# Jumper_Board_V3_0.net
KiCad netlist of a schematic drawn in EAGLE
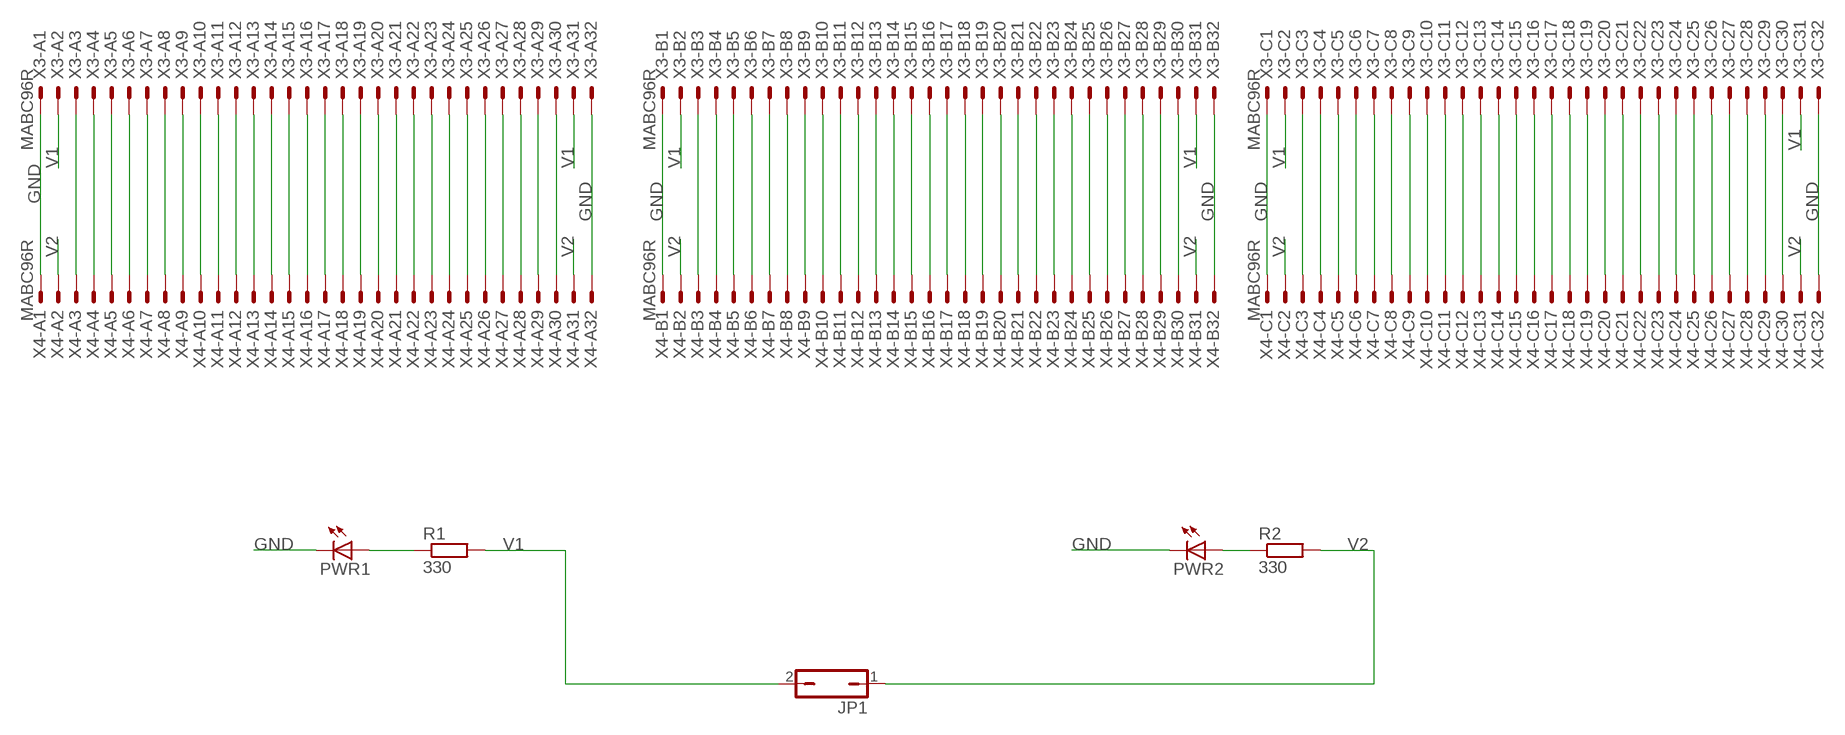
[diagram p0: schematic, sheet 1]

(export (version "E")
  (design (tool "Eeschema 10.0.6"))
  (components
    (comp (ref "JP1")
      (value "JP1Q")
      (footprint "eagle-import:JP1")
      (libsource (lib "eagle-import") (part "JP1Q"))
    )
    (comp (ref "PWR1")
      (value "LED5MM")
      (footprint "eagle-import:LED5MM")
      (libsource (lib "eagle-import") (part "LED5MM"))
    )
    (comp (ref "PWR2")
      (value "LED5MM")
      (footprint "eagle-import:LED5MM")
      (libsource (lib "eagle-import") (part "LED5MM"))
    )
    (comp (ref "R1")
      (value "330")
      (footprint "eagle-import:0207_10")
      (libsource (lib "eagle-import") (part "R0207/10"))
    )
    (comp (ref "R2")
      (value "330")
      (footprint "eagle-import:0207_10")
      (libsource (lib "eagle-import") (part "R0207/10"))
    )
    (comp (ref "X3")
      (value "MABC96R")
      (footprint "eagle-import:MABC96R")
      (libsource (lib "eagle-import") (part "MABC96R"))
    )
    (comp (ref "X4")
      (value "MABC96R")
      (footprint "eagle-import:MABC96R")
      (libsource (lib "eagle-import") (part "MABC96R"))
    )
  )
  (nets
    (net (code "1") (name "/GND") (class "Default")
      (node (ref "PWR1") (pin "K") (pinfunction "C_K") (pintype "passive"))
      (node (ref "PWR2") (pin "K") (pinfunction "C_K") (pintype "passive"))
      (node (ref "X3") (pin "A1") (pinfunction "S_A1") (pintype "passive"))
      (node (ref "X3") (pin "A32") (pinfunction "S_A32") (pintype "passive"))
      (node (ref "X3") (pin "B1") (pinfunction "S_B1") (pintype "passive"))
      (node (ref "X3") (pin "B32") (pinfunction "S_B32") (pintype "passive"))
      (node (ref "X3") (pin "C1") (pinfunction "S_C1") (pintype "passive"))
      (node (ref "X3") (pin "C32") (pinfunction "S_C32") (pintype "passive"))
      (node (ref "X4") (pin "A1") (pinfunction "S_A1") (pintype "passive"))
      (node (ref "X4") (pin "A32") (pinfunction "S_A32") (pintype "passive"))
      (node (ref "X4") (pin "B1") (pinfunction "S_B1") (pintype "passive"))
      (node (ref "X4") (pin "B32") (pinfunction "S_B32") (pintype "passive"))
      (node (ref "X4") (pin "C1") (pinfunction "S_C1") (pintype "passive"))
      (node (ref "X4") (pin "C32") (pinfunction "S_C32") (pintype "passive"))
    )
    (net (code "2") (name "/V1") (class "Default")
      (node (ref "JP1") (pin "2") (pinfunction "2_2") (pintype "passive"))
      (node (ref "R1") (pin "2") (pinfunction "2_2") (pintype "passive"))
      (node (ref "X3") (pin "A2") (pinfunction "S_A2") (pintype "passive"))
      (node (ref "X3") (pin "A31") (pinfunction "S_A31") (pintype "passive"))
      (node (ref "X3") (pin "B2") (pinfunction "S_B2") (pintype "passive"))
      (node (ref "X3") (pin "B31") (pinfunction "S_B31") (pintype "passive"))
      (node (ref "X3") (pin "C2") (pinfunction "S_C2") (pintype "passive"))
      (node (ref "X3") (pin "C31") (pinfunction "S_C31") (pintype "passive"))
    )
    (net (code "3") (name "/V2") (class "Default")
      (node (ref "JP1") (pin "1") (pinfunction "1_1") (pintype "passive"))
      (node (ref "R2") (pin "2") (pinfunction "2_2") (pintype "passive"))
      (node (ref "X4") (pin "A2") (pinfunction "S_A2") (pintype "passive"))
      (node (ref "X4") (pin "A31") (pinfunction "S_A31") (pintype "passive"))
      (node (ref "X4") (pin "B2") (pinfunction "S_B2") (pintype "passive"))
      (node (ref "X4") (pin "B31") (pinfunction "S_B31") (pintype "passive"))
      (node (ref "X4") (pin "C2") (pinfunction "S_C2") (pintype "passive"))
      (node (ref "X4") (pin "C31") (pinfunction "S_C31") (pintype "passive"))
    )
    (net (code "4") (name "Net-(PWR1-PadA)") (class "Default")
      (node (ref "PWR1") (pin "A") (pinfunction "A_A") (pintype "passive"))
      (node (ref "R1") (pin "1") (pinfunction "1_1") (pintype "passive"))
    )
    (net (code "5") (name "Net-(PWR2-PadA)") (class "Default")
      (node (ref "PWR2") (pin "A") (pinfunction "A_A") (pintype "passive"))
      (node (ref "R2") (pin "1") (pinfunction "1_1") (pintype "passive"))
    )
    (net (code "6") (name "Net-(X3AA-S)") (class "Default")
      (node (ref "X3") (pin "A4") (pinfunction "S_A4") (pintype "passive"))
      (node (ref "X4") (pin "A4") (pinfunction "S_A4") (pintype "passive"))
    )
    (net (code "7") (name "Net-(X3AB-S)") (class "Default")
      (node (ref "X3") (pin "A5") (pinfunction "S_A5") (pintype "passive"))
      (node (ref "X4") (pin "A5") (pinfunction "S_A5") (pintype "passive"))
    )
    (net (code "8") (name "Net-(X3AC-S)") (class "Default")
      (node (ref "X3") (pin "A6") (pinfunction "S_A6") (pintype "passive"))
      (node (ref "X4") (pin "A6") (pinfunction "S_A6") (pintype "passive"))
    )
    (net (code "9") (name "Net-(X3AD-S)") (class "Default")
      (node (ref "X3") (pin "A7") (pinfunction "S_A7") (pintype "passive"))
      (node (ref "X4") (pin "A7") (pinfunction "S_A7") (pintype "passive"))
    )
    (net (code "10") (name "Net-(X3AE-S)") (class "Default")
      (node (ref "X3") (pin "A8") (pinfunction "S_A8") (pintype "passive"))
      (node (ref "X4") (pin "A8") (pinfunction "S_A8") (pintype "passive"))
    )
    (net (code "11") (name "Net-(X3AF-S)") (class "Default")
      (node (ref "X3") (pin "A9") (pinfunction "S_A9") (pintype "passive"))
      (node (ref "X4") (pin "A9") (pinfunction "S_A9") (pintype "passive"))
    )
    (net (code "12") (name "Net-(X3AH-S)") (class "Default")
      (node (ref "X3") (pin "B10") (pinfunction "S_B10") (pintype "passive"))
      (node (ref "X4") (pin "B10") (pinfunction "S_B10") (pintype "passive"))
    )
    (net (code "13") (name "Net-(X3AI-S)") (class "Default")
      (node (ref "X3") (pin "B11") (pinfunction "S_B11") (pintype "passive"))
      (node (ref "X4") (pin "B11") (pinfunction "S_B11") (pintype "passive"))
    )
    (net (code "14") (name "Net-(X3AJ-S)") (class "Default")
      (node (ref "X3") (pin "B12") (pinfunction "S_B12") (pintype "passive"))
      (node (ref "X4") (pin "B12") (pinfunction "S_B12") (pintype "passive"))
    )
    (net (code "15") (name "Net-(X3AK-S)") (class "Default")
      (node (ref "X3") (pin "B13") (pinfunction "S_B13") (pintype "passive"))
      (node (ref "X4") (pin "B13") (pinfunction "S_B13") (pintype "passive"))
    )
    (net (code "16") (name "Net-(X3AL-S)") (class "Default")
      (node (ref "X3") (pin "B14") (pinfunction "S_B14") (pintype "passive"))
      (node (ref "X4") (pin "B14") (pinfunction "S_B14") (pintype "passive"))
    )
    (net (code "17") (name "Net-(X3AM-S)") (class "Default")
      (node (ref "X3") (pin "B15") (pinfunction "S_B15") (pintype "passive"))
      (node (ref "X4") (pin "B15") (pinfunction "S_B15") (pintype "passive"))
    )
    (net (code "18") (name "Net-(X3AN-S)") (class "Default")
      (node (ref "X3") (pin "B16") (pinfunction "S_B16") (pintype "passive"))
      (node (ref "X4") (pin "B16") (pinfunction "S_B16") (pintype "passive"))
    )
    (net (code "19") (name "Net-(X3AO-S)") (class "Default")
      (node (ref "X3") (pin "B17") (pinfunction "S_B17") (pintype "passive"))
      (node (ref "X4") (pin "B17") (pinfunction "S_B17") (pintype "passive"))
    )
    (net (code "20") (name "Net-(X3AP-S)") (class "Default")
      (node (ref "X3") (pin "B18") (pinfunction "S_B18") (pintype "passive"))
      (node (ref "X4") (pin "B18") (pinfunction "S_B18") (pintype "passive"))
    )
    (net (code "21") (name "Net-(X3AQ-S)") (class "Default")
      (node (ref "X3") (pin "B19") (pinfunction "S_B19") (pintype "passive"))
      (node (ref "X4") (pin "B19") (pinfunction "S_B19") (pintype "passive"))
    )
    (net (code "22") (name "Net-(X3AS-S)") (class "Default")
      (node (ref "X3") (pin "B20") (pinfunction "S_B20") (pintype "passive"))
      (node (ref "X4") (pin "B20") (pinfunction "S_B20") (pintype "passive"))
    )
    (net (code "23") (name "Net-(X3AT-S)") (class "Default")
      (node (ref "X3") (pin "B21") (pinfunction "S_B21") (pintype "passive"))
      (node (ref "X4") (pin "B21") (pinfunction "S_B21") (pintype "passive"))
    )
    (net (code "24") (name "Net-(X3AU-S)") (class "Default")
      (node (ref "X3") (pin "B22") (pinfunction "S_B22") (pintype "passive"))
      (node (ref "X4") (pin "B22") (pinfunction "S_B22") (pintype "passive"))
    )
    (net (code "25") (name "Net-(X3AV-S)") (class "Default")
      (node (ref "X3") (pin "B23") (pinfunction "S_B23") (pintype "passive"))
      (node (ref "X4") (pin "B23") (pinfunction "S_B23") (pintype "passive"))
    )
    (net (code "26") (name "Net-(X3AW-S)") (class "Default")
      (node (ref "X3") (pin "B24") (pinfunction "S_B24") (pintype "passive"))
      (node (ref "X4") (pin "B24") (pinfunction "S_B24") (pintype "passive"))
    )
    (net (code "27") (name "Net-(X3AX-S)") (class "Default")
      (node (ref "X3") (pin "B25") (pinfunction "S_B25") (pintype "passive"))
      (node (ref "X4") (pin "B25") (pinfunction "S_B25") (pintype "passive"))
    )
    (net (code "28") (name "Net-(X3AY-S)") (class "Default")
      (node (ref "X3") (pin "B26") (pinfunction "S_B26") (pintype "passive"))
      (node (ref "X4") (pin "B26") (pinfunction "S_B26") (pintype "passive"))
    )
    (net (code "29") (name "Net-(X3AZ-S)") (class "Default")
      (node (ref "X3") (pin "B27") (pinfunction "S_B27") (pintype "passive"))
      (node (ref "X4") (pin "B27") (pinfunction "S_B27") (pintype "passive"))
    )
    (net (code "30") (name "Net-(X3B-S)") (class "Default")
      (node (ref "X3") (pin "A10") (pinfunction "S_A10") (pintype "passive"))
      (node (ref "X4") (pin "A10") (pinfunction "S_A10") (pintype "passive"))
    )
    (net (code "31") (name "Net-(X3BA-S)") (class "Default")
      (node (ref "X3") (pin "B28") (pinfunction "S_B28") (pintype "passive"))
      (node (ref "X4") (pin "B28") (pinfunction "S_B28") (pintype "passive"))
    )
    (net (code "32") (name "Net-(X3BB-S)") (class "Default")
      (node (ref "X3") (pin "B29") (pinfunction "S_B29") (pintype "passive"))
      (node (ref "X4") (pin "B29") (pinfunction "S_B29") (pintype "passive"))
    )
    (net (code "33") (name "Net-(X3BC-S)") (class "Default")
      (node (ref "X3") (pin "B3") (pinfunction "S_B3") (pintype "passive"))
      (node (ref "X4") (pin "B3") (pinfunction "S_B3") (pintype "passive"))
    )
    (net (code "34") (name "Net-(X3BD-S)") (class "Default")
      (node (ref "X3") (pin "B30") (pinfunction "S_B30") (pintype "passive"))
      (node (ref "X4") (pin "B30") (pinfunction "S_B30") (pintype "passive"))
    )
    (net (code "35") (name "Net-(X3BG-S)") (class "Default")
      (node (ref "X3") (pin "B4") (pinfunction "S_B4") (pintype "passive"))
      (node (ref "X4") (pin "B4") (pinfunction "S_B4") (pintype "passive"))
    )
    (net (code "36") (name "Net-(X3BH-S)") (class "Default")
      (node (ref "X3") (pin "B5") (pinfunction "S_B5") (pintype "passive"))
      (node (ref "X4") (pin "B5") (pinfunction "S_B5") (pintype "passive"))
    )
    (net (code "37") (name "Net-(X3BI-S)") (class "Default")
      (node (ref "X3") (pin "B6") (pinfunction "S_B6") (pintype "passive"))
      (node (ref "X4") (pin "B6") (pinfunction "S_B6") (pintype "passive"))
    )
    (net (code "38") (name "Net-(X3BJ-S)") (class "Default")
      (node (ref "X3") (pin "B7") (pinfunction "S_B7") (pintype "passive"))
      (node (ref "X4") (pin "B7") (pinfunction "S_B7") (pintype "passive"))
    )
    (net (code "39") (name "Net-(X3BK-S)") (class "Default")
      (node (ref "X3") (pin "B8") (pinfunction "S_B8") (pintype "passive"))
      (node (ref "X4") (pin "B8") (pinfunction "S_B8") (pintype "passive"))
    )
    (net (code "40") (name "Net-(X3BL-S)") (class "Default")
      (node (ref "X3") (pin "B9") (pinfunction "S_B9") (pintype "passive"))
      (node (ref "X4") (pin "B9") (pinfunction "S_B9") (pintype "passive"))
    )
    (net (code "41") (name "Net-(X3BN-S)") (class "Default")
      (node (ref "X3") (pin "C10") (pinfunction "S_C10") (pintype "passive"))
      (node (ref "X4") (pin "C10") (pinfunction "S_C10") (pintype "passive"))
    )
    (net (code "42") (name "Net-(X3BO-S)") (class "Default")
      (node (ref "X3") (pin "C11") (pinfunction "S_C11") (pintype "passive"))
      (node (ref "X4") (pin "C11") (pinfunction "S_C11") (pintype "passive"))
    )
    (net (code "43") (name "Net-(X3BP-S)") (class "Default")
      (node (ref "X3") (pin "C12") (pinfunction "S_C12") (pintype "passive"))
      (node (ref "X4") (pin "C12") (pinfunction "S_C12") (pintype "passive"))
    )
    (net (code "44") (name "Net-(X3BQ-S)") (class "Default")
      (node (ref "X3") (pin "C13") (pinfunction "S_C13") (pintype "passive"))
      (node (ref "X4") (pin "C13") (pinfunction "S_C13") (pintype "passive"))
    )
    (net (code "45") (name "Net-(X3BR-S)") (class "Default")
      (node (ref "X3") (pin "C14") (pinfunction "S_C14") (pintype "passive"))
      (node (ref "X4") (pin "C14") (pinfunction "S_C14") (pintype "passive"))
    )
    (net (code "46") (name "Net-(X3BS-S)") (class "Default")
      (node (ref "X3") (pin "C15") (pinfunction "S_C15") (pintype "passive"))
      (node (ref "X4") (pin "C15") (pinfunction "S_C15") (pintype "passive"))
    )
    (net (code "47") (name "Net-(X3BT-S)") (class "Default")
      (node (ref "X3") (pin "C16") (pinfunction "S_C16") (pintype "passive"))
      (node (ref "X4") (pin "C16") (pinfunction "S_C16") (pintype "passive"))
    )
    (net (code "48") (name "Net-(X3BU-S)") (class "Default")
      (node (ref "X3") (pin "C17") (pinfunction "S_C17") (pintype "passive"))
      (node (ref "X4") (pin "C17") (pinfunction "S_C17") (pintype "passive"))
    )
    (net (code "49") (name "Net-(X3BV-S)") (class "Default")
      (node (ref "X3") (pin "C18") (pinfunction "S_C18") (pintype "passive"))
      (node (ref "X4") (pin "C18") (pinfunction "S_C18") (pintype "passive"))
    )
    (net (code "50") (name "Net-(X3BW-S)") (class "Default")
      (node (ref "X3") (pin "C19") (pinfunction "S_C19") (pintype "passive"))
      (node (ref "X4") (pin "C19") (pinfunction "S_C19") (pintype "passive"))
    )
    (net (code "51") (name "Net-(X3BY-S)") (class "Default")
      (node (ref "X3") (pin "C20") (pinfunction "S_C20") (pintype "passive"))
      (node (ref "X4") (pin "C20") (pinfunction "S_C20") (pintype "passive"))
    )
    (net (code "52") (name "Net-(X3BZ-S)") (class "Default")
      (node (ref "X3") (pin "C21") (pinfunction "S_C21") (pintype "passive"))
      (node (ref "X4") (pin "C21") (pinfunction "S_C21") (pintype "passive"))
    )
    (net (code "53") (name "Net-(X3C-S)") (class "Default")
      (node (ref "X3") (pin "A11") (pinfunction "S_A11") (pintype "passive"))
      (node (ref "X4") (pin "A11") (pinfunction "S_A11") (pintype "passive"))
    )
    (net (code "54") (name "Net-(X3CA-S)") (class "Default")
      (node (ref "X3") (pin "C22") (pinfunction "S_C22") (pintype "passive"))
      (node (ref "X4") (pin "C22") (pinfunction "S_C22") (pintype "passive"))
    )
    (net (code "55") (name "Net-(X3CB-S)") (class "Default")
      (node (ref "X3") (pin "C23") (pinfunction "S_C23") (pintype "passive"))
      (node (ref "X4") (pin "C23") (pinfunction "S_C23") (pintype "passive"))
    )
    (net (code "56") (name "Net-(X3CC-S)") (class "Default")
      (node (ref "X3") (pin "C24") (pinfunction "S_C24") (pintype "passive"))
      (node (ref "X4") (pin "C24") (pinfunction "S_C24") (pintype "passive"))
    )
    (net (code "57") (name "Net-(X3CD-S)") (class "Default")
      (node (ref "X3") (pin "C25") (pinfunction "S_C25") (pintype "passive"))
      (node (ref "X4") (pin "C25") (pinfunction "S_C25") (pintype "passive"))
    )
    (net (code "58") (name "Net-(X3CE-S)") (class "Default")
      (node (ref "X3") (pin "C26") (pinfunction "S_C26") (pintype "passive"))
      (node (ref "X4") (pin "C26") (pinfunction "S_C26") (pintype "passive"))
    )
    (net (code "59") (name "Net-(X3CF-S)") (class "Default")
      (node (ref "X3") (pin "C27") (pinfunction "S_C27") (pintype "passive"))
      (node (ref "X4") (pin "C27") (pinfunction "S_C27") (pintype "passive"))
    )
    (net (code "60") (name "Net-(X3CG-S)") (class "Default")
      (node (ref "X3") (pin "C28") (pinfunction "S_C28") (pintype "passive"))
      (node (ref "X4") (pin "C28") (pinfunction "S_C28") (pintype "passive"))
    )
    (net (code "61") (name "Net-(X3CH-S)") (class "Default")
      (node (ref "X3") (pin "C29") (pinfunction "S_C29") (pintype "passive"))
      (node (ref "X4") (pin "C29") (pinfunction "S_C29") (pintype "passive"))
    )
    (net (code "62") (name "Net-(X3CI-S)") (class "Default")
      (node (ref "X3") (pin "C3") (pinfunction "S_C3") (pintype "passive"))
      (node (ref "X4") (pin "C3") (pinfunction "S_C3") (pintype "passive"))
    )
    (net (code "63") (name "Net-(X3CJ-S)") (class "Default")
      (node (ref "X3") (pin "C30") (pinfunction "S_C30") (pintype "passive"))
      (node (ref "X4") (pin "C30") (pinfunction "S_C30") (pintype "passive"))
    )
    (net (code "64") (name "Net-(X3CM-S)") (class "Default")
      (node (ref "X3") (pin "C4") (pinfunction "S_C4") (pintype "passive"))
      (node (ref "X4") (pin "C4") (pinfunction "S_C4") (pintype "passive"))
    )
    (net (code "65") (name "Net-(X3CN-S)") (class "Default")
      (node (ref "X3") (pin "C5") (pinfunction "S_C5") (pintype "passive"))
      (node (ref "X4") (pin "C5") (pinfunction "S_C5") (pintype "passive"))
    )
    (net (code "66") (name "Net-(X3CO-S)") (class "Default")
      (node (ref "X3") (pin "C6") (pinfunction "S_C6") (pintype "passive"))
      (node (ref "X4") (pin "C6") (pinfunction "S_C6") (pintype "passive"))
    )
    (net (code "67") (name "Net-(X3CP-S)") (class "Default")
      (node (ref "X3") (pin "C7") (pinfunction "S_C7") (pintype "passive"))
      (node (ref "X4") (pin "C7") (pinfunction "S_C7") (pintype "passive"))
    )
    (net (code "68") (name "Net-(X3CQ-S)") (class "Default")
      (node (ref "X3") (pin "C8") (pinfunction "S_C8") (pintype "passive"))
      (node (ref "X4") (pin "C8") (pinfunction "S_C8") (pintype "passive"))
    )
    (net (code "69") (name "Net-(X3CR-S)") (class "Default")
      (node (ref "X3") (pin "C9") (pinfunction "S_C9") (pintype "passive"))
      (node (ref "X4") (pin "C9") (pinfunction "S_C9") (pintype "passive"))
    )
    (net (code "70") (name "Net-(X3D-S)") (class "Default")
      (node (ref "X3") (pin "A12") (pinfunction "S_A12") (pintype "passive"))
      (node (ref "X4") (pin "A12") (pinfunction "S_A12") (pintype "passive"))
    )
    (net (code "71") (name "Net-(X3E-S)") (class "Default")
      (node (ref "X3") (pin "A13") (pinfunction "S_A13") (pintype "passive"))
      (node (ref "X4") (pin "A13") (pinfunction "S_A13") (pintype "passive"))
    )
    (net (code "72") (name "Net-(X3F-S)") (class "Default")
      (node (ref "X3") (pin "A14") (pinfunction "S_A14") (pintype "passive"))
      (node (ref "X4") (pin "A14") (pinfunction "S_A14") (pintype "passive"))
    )
    (net (code "73") (name "Net-(X3G-S)") (class "Default")
      (node (ref "X3") (pin "A15") (pinfunction "S_A15") (pintype "passive"))
      (node (ref "X4") (pin "A15") (pinfunction "S_A15") (pintype "passive"))
    )
    (net (code "74") (name "Net-(X3H-S)") (class "Default")
      (node (ref "X3") (pin "A16") (pinfunction "S_A16") (pintype "passive"))
      (node (ref "X4") (pin "A16") (pinfunction "S_A16") (pintype "passive"))
    )
    (net (code "75") (name "Net-(X3I-S)") (class "Default")
      (node (ref "X3") (pin "A17") (pinfunction "S_A17") (pintype "passive"))
      (node (ref "X4") (pin "A17") (pinfunction "S_A17") (pintype "passive"))
    )
    (net (code "76") (name "Net-(X3J-S)") (class "Default")
      (node (ref "X3") (pin "A18") (pinfunction "S_A18") (pintype "passive"))
      (node (ref "X4") (pin "A18") (pinfunction "S_A18") (pintype "passive"))
    )
    (net (code "77") (name "Net-(X3K-S)") (class "Default")
      (node (ref "X3") (pin "A19") (pinfunction "S_A19") (pintype "passive"))
      (node (ref "X4") (pin "A19") (pinfunction "S_A19") (pintype "passive"))
    )
    (net (code "78") (name "Net-(X3M-S)") (class "Default")
      (node (ref "X3") (pin "A20") (pinfunction "S_A20") (pintype "passive"))
      (node (ref "X4") (pin "A20") (pinfunction "S_A20") (pintype "passive"))
    )
    (net (code "79") (name "Net-(X3N-S)") (class "Default")
      (node (ref "X3") (pin "A21") (pinfunction "S_A21") (pintype "passive"))
      (node (ref "X4") (pin "A21") (pinfunction "S_A21") (pintype "passive"))
    )
    (net (code "80") (name "Net-(X3O-S)") (class "Default")
      (node (ref "X3") (pin "A22") (pinfunction "S_A22") (pintype "passive"))
      (node (ref "X4") (pin "A22") (pinfunction "S_A22") (pintype "passive"))
    )
    (net (code "81") (name "Net-(X3P-S)") (class "Default")
      (node (ref "X3") (pin "A23") (pinfunction "S_A23") (pintype "passive"))
      (node (ref "X4") (pin "A23") (pinfunction "S_A23") (pintype "passive"))
    )
    (net (code "82") (name "Net-(X3Q-S)") (class "Default")
      (node (ref "X3") (pin "A24") (pinfunction "S_A24") (pintype "passive"))
      (node (ref "X4") (pin "A24") (pinfunction "S_A24") (pintype "passive"))
    )
    (net (code "83") (name "Net-(X3R-S)") (class "Default")
      (node (ref "X3") (pin "A25") (pinfunction "S_A25") (pintype "passive"))
      (node (ref "X4") (pin "A25") (pinfunction "S_A25") (pintype "passive"))
    )
    (net (code "84") (name "Net-(X3S-S)") (class "Default")
      (node (ref "X3") (pin "A26") (pinfunction "S_A26") (pintype "passive"))
      (node (ref "X4") (pin "A26") (pinfunction "S_A26") (pintype "passive"))
    )
    (net (code "85") (name "Net-(X3T-S)") (class "Default")
      (node (ref "X3") (pin "A27") (pinfunction "S_A27") (pintype "passive"))
      (node (ref "X4") (pin "A27") (pinfunction "S_A27") (pintype "passive"))
    )
    (net (code "86") (name "Net-(X3U-S)") (class "Default")
      (node (ref "X3") (pin "A28") (pinfunction "S_A28") (pintype "passive"))
      (node (ref "X4") (pin "A28") (pinfunction "S_A28") (pintype "passive"))
    )
    (net (code "87") (name "Net-(X3V-S)") (class "Default")
      (node (ref "X3") (pin "A29") (pinfunction "S_A29") (pintype "passive"))
      (node (ref "X4") (pin "A29") (pinfunction "S_A29") (pintype "passive"))
    )
    (net (code "88") (name "Net-(X3W-S)") (class "Default")
      (node (ref "X3") (pin "A3") (pinfunction "S_A3") (pintype "passive"))
      (node (ref "X4") (pin "A3") (pinfunction "S_A3") (pintype "passive"))
    )
    (net (code "89") (name "Net-(X3X-S)") (class "Default")
      (node (ref "X3") (pin "A30") (pinfunction "S_A30") (pintype "passive"))
      (node (ref "X4") (pin "A30") (pinfunction "S_A30") (pintype "passive"))
    )
  )
)
